# RoverMux.net
KiCad netlist of a schematic drawn in EAGLE
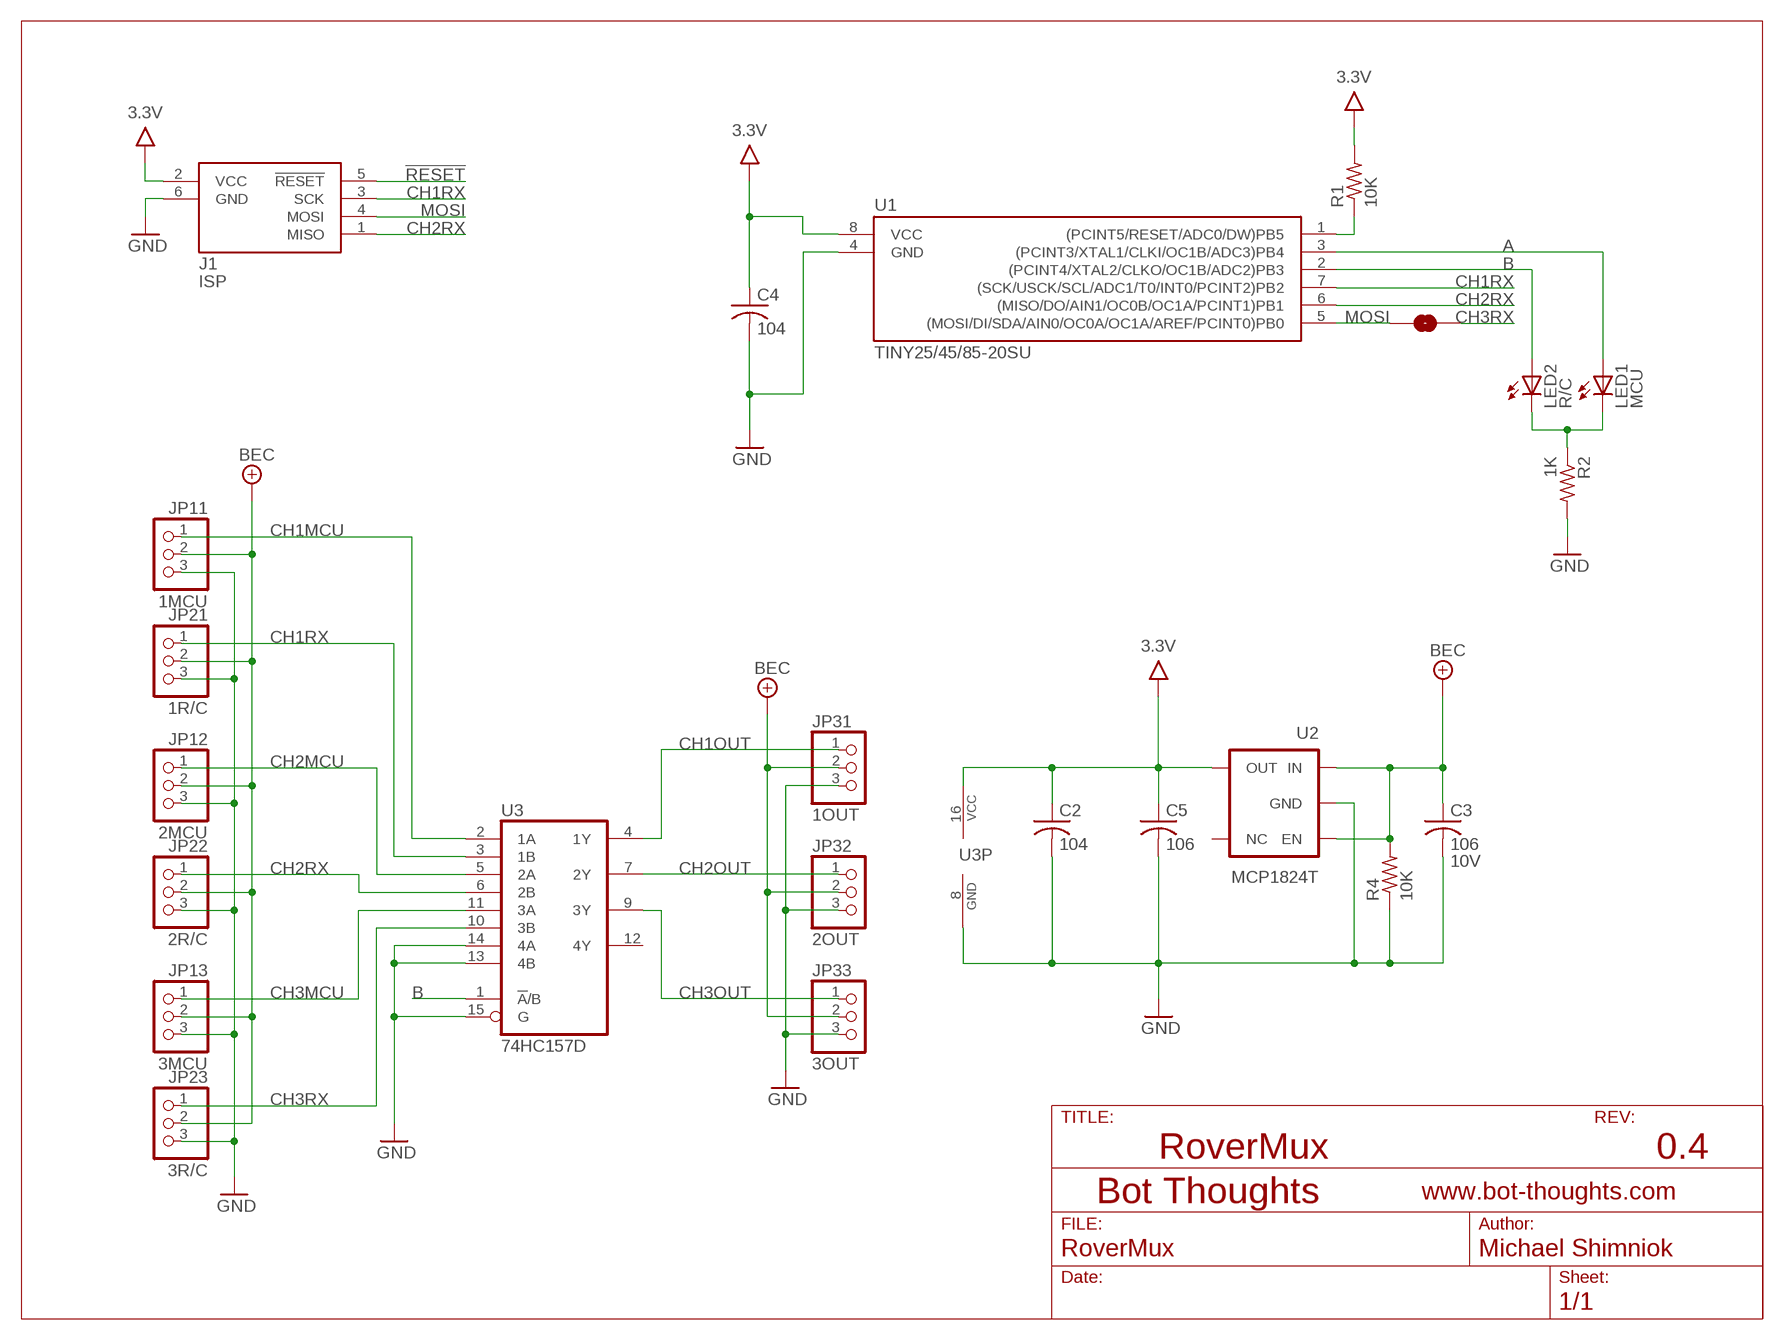
[diagram p0: schematic, sheet 1]

(export (version "E")
  (design (tool "Eeschema 10.0.6"))
  (components
    (comp (ref "C2")
      (value "104")
      (footprint "eagle-import:C0603")
      (fields (field (name "PARTNO") "C1608X7R1E104K080AA"))
      (libsource (lib "eagle-import") (part "C-USC0603"))
    )
    (comp (ref "C3")
      (value "106")
      (footprint "eagle-import:C0603")
      (fields (field (name "PARTNO") "CL10A106MP8NNNC") (field (name "VOLTAGE") "10V"))
      (libsource (lib "eagle-import") (part "C-USC0603"))
    )
    (comp (ref "C4")
      (value "104")
      (footprint "eagle-import:C0603")
      (fields (field (name "PARTNO") "C1608X7R1E104K080AA"))
      (libsource (lib "eagle-import") (part "C-USC0603"))
    )
    (comp (ref "C5")
      (value "106")
      (footprint "eagle-import:C0603")
      (fields (field (name "PARTNO") "CL10A106MP8NNNC"))
      (libsource (lib "eagle-import") (part "C-USC0603"))
    )
    (comp (ref "J1")
      (value "ISP")
      (footprint "eagle-import:CON6P2R")
      (libsource (lib "eagle-import") (part "AVRISP6"))
    )
    (comp (ref "JP11")
      (value "1MCU")
      (footprint "eagle-import:1X03-S")
      (libsource (lib "eagle-import") (part "PINHD-1X03_2.54-S"))
    )
    (comp (ref "JP12")
      (value "2MCU")
      (footprint "eagle-import:1X03-S")
      (libsource (lib "eagle-import") (part "PINHD-1X03_2.54-S"))
    )
    (comp (ref "JP13")
      (value "3MCU")
      (footprint "eagle-import:1X03-S")
      (libsource (lib "eagle-import") (part "PINHD-1X03_2.54-S"))
    )
    (comp (ref "JP21")
      (value "1R/C")
      (footprint "eagle-import:1X03-S")
      (libsource (lib "eagle-import") (part "PINHD-1X03_2.54-S"))
    )
    (comp (ref "JP22")
      (value "2R/C")
      (footprint "eagle-import:1X03-S")
      (libsource (lib "eagle-import") (part "PINHD-1X03_2.54-S"))
    )
    (comp (ref "JP23")
      (value "3R/C")
      (footprint "eagle-import:1X03-S")
      (libsource (lib "eagle-import") (part "PINHD-1X03_2.54-S"))
    )
    (comp (ref "JP31")
      (value "1OUT")
      (footprint "eagle-import:1X03-S")
      (libsource (lib "eagle-import") (part "PINHD-1X03_2.54-S"))
    )
    (comp (ref "JP32")
      (value "2OUT")
      (footprint "eagle-import:1X03-S")
      (libsource (lib "eagle-import") (part "PINHD-1X03_2.54-S"))
    )
    (comp (ref "JP33")
      (value "3OUT")
      (footprint "eagle-import:1X03-S")
      (libsource (lib "eagle-import") (part "PINHD-1X03_2.54-S"))
    )
    (comp (ref "LED1")
      (value "MCU")
      (footprint "eagle-import:CHIPLED_1206")
      (fields (field (name "PARTNO") "LH N974-KN-1"))
      (libsource (lib "eagle-import") (part "LEDCHIPLED_1206"))
    )
    (comp (ref "LED2")
      (value "R/C")
      (footprint "eagle-import:CHIPLED_1206")
      (fields (field (name "PARTNO") "LG N971-KN-1"))
      (libsource (lib "eagle-import") (part "LEDCHIPLED_1206"))
    )
    (comp (ref "R1")
      (value "10K")
      (footprint "eagle-import:R0603")
      (fields (field (name "PARTNO") "1622829-1"))
      (libsource (lib "eagle-import") (part "R-US_R0603"))
    )
    (comp (ref "R2")
      (value "1K")
      (footprint "eagle-import:R0603")
      (fields (field (name "PARTNO") "RC0603JR-07330RL"))
      (libsource (lib "eagle-import") (part "R-US_R0603"))
    )
    (comp (ref "R4")
      (value "10K")
      (footprint "eagle-import:R0603")
      (fields (field (name "PARTNO") "1622829-1"))
      (libsource (lib "eagle-import") (part "R-US_R0603"))
    )
    (comp (ref "SJ1")
      (value "CH3")
      (footprint "eagle-import:SJ_2S-NOTRACE")
      (libsource (lib "eagle-import") (part "SOLDERJUMPERNC2"))
    )
    (comp (ref "U1")
      (value "TINY25/45/85-20SU")
      (footprint "eagle-import:SOIC8")
      (libsource (lib "eagle-import") (part "TINY25/45/85-20SU"))
    )
    (comp (ref "U2")
      (value "MCP1824T")
      (footprint "eagle-import:SOT23-5")
      (fields (field (name "PARTNO") "MCP1824T-5002E/OT"))
      (libsource (lib "eagle-import") (part "MCP1801"))
    )
    (comp (ref "U3")
      (value "74HC157D")
      (footprint "eagle-import:SO16")
      (fields (field (name "PARTNO") "74HCT157D,652"))
      (libsource (lib "eagle-import") (part "74157DLS"))
    )
  )
  (nets
    (net (code "1") (name "/A") (class "Default")
      (node (ref "LED1") (pin "A") (pinfunction "A_A") (pintype "passive"))
      (node (ref "U1") (pin "3") (pinfunction "(PCINT3/XTAL1/CLKI/OC1B/ADC3)PB4_3") (pintype "bidirectional"))
    )
    (net (code "2") (name "/B") (class "Default")
      (node (ref "LED2") (pin "A") (pinfunction "A_A") (pintype "passive"))
      (node (ref "U1") (pin "2") (pinfunction "(PCINT4/XTAL2/CLKO/OC1B/ADC2)PB3_2") (pintype "bidirectional"))
      (node (ref "U3") (pin "1") (pinfunction "~{A}/B_1") (pintype "input"))
    )
    (net (code "3") (name "/CH1MCU") (class "Default")
      (node (ref "JP11") (pin "1") (pinfunction "1_1") (pintype "passive"))
      (node (ref "U3") (pin "2") (pinfunction "1A_2") (pintype "input"))
    )
    (net (code "4") (name "/CH1OUT") (class "Default")
      (node (ref "JP31") (pin "1") (pinfunction "1_1") (pintype "passive"))
      (node (ref "U3") (pin "4") (pinfunction "1Y_4") (pintype "output"))
    )
    (net (code "5") (name "/CH1RX") (class "Default")
      (node (ref "J1") (pin "3") (pinfunction "SCK_3") (pintype "output"))
      (node (ref "JP21") (pin "1") (pinfunction "1_1") (pintype "passive"))
      (node (ref "U1") (pin "7") (pinfunction "(SCK/USCK/SCL/ADC1/T0/INT0/PCINT2)PB2_7") (pintype "bidirectional"))
      (node (ref "U3") (pin "3") (pinfunction "1B_3") (pintype "input"))
    )
    (net (code "6") (name "/CH2MCU") (class "Default")
      (node (ref "JP12") (pin "1") (pinfunction "1_1") (pintype "passive"))
      (node (ref "U3") (pin "5") (pinfunction "2A_5") (pintype "input"))
    )
    (net (code "7") (name "/CH2OUT") (class "Default")
      (node (ref "JP32") (pin "1") (pinfunction "1_1") (pintype "passive"))
      (node (ref "U3") (pin "7") (pinfunction "2Y_7") (pintype "output"))
    )
    (net (code "8") (name "/CH2RX") (class "Default")
      (node (ref "J1") (pin "1") (pinfunction "MISO_1") (pintype "input"))
      (node (ref "JP22") (pin "1") (pinfunction "1_1") (pintype "passive"))
      (node (ref "U1") (pin "6") (pinfunction "(MISO/DO/AIN1/OC0B/OC1A/PCINT1)PB1_6") (pintype "bidirectional"))
      (node (ref "U3") (pin "6") (pinfunction "2B_6") (pintype "input"))
    )
    (net (code "9") (name "/CH3MCU") (class "Default")
      (node (ref "JP13") (pin "1") (pinfunction "1_1") (pintype "passive"))
      (node (ref "U3") (pin "11") (pinfunction "3A_11") (pintype "input"))
    )
    (net (code "10") (name "/CH3OUT") (class "Default")
      (node (ref "JP33") (pin "1") (pinfunction "1_1") (pintype "passive"))
      (node (ref "U3") (pin "9") (pinfunction "3Y_9") (pintype "output"))
    )
    (net (code "11") (name "/CH3RX") (class "Default")
      (node (ref "JP23") (pin "1") (pinfunction "1_1") (pintype "passive"))
      (node (ref "SJ1") (pin "2") (pinfunction "2_2") (pintype "passive"))
      (node (ref "U3") (pin "10") (pinfunction "3B_10") (pintype "input"))
    )
    (net (code "12") (name "/MOSI") (class "Default")
      (node (ref "J1") (pin "4") (pinfunction "MOSI_4") (pintype "output"))
      (node (ref "SJ1") (pin "1") (pinfunction "1_1") (pintype "passive"))
      (node (ref "U1") (pin "5") (pinfunction "(MOSI/DI/SDA/AIN0/OC0A/OC1A/AREF/PCINT0)PB0_5") (pintype "bidirectional"))
    )
    (net (code "13") (name "/~{RESET}") (class "Default")
      (node (ref "J1") (pin "5") (pinfunction "~{RESET}_5") (pintype "output"))
      (node (ref "R1") (pin "1") (pinfunction "1_1") (pintype "passive"))
      (node (ref "U1") (pin "1") (pinfunction "(PCINT5/RESET/ADC0/DW)PB5_1") (pintype "bidirectional"))
    )
    (net (code "14") (name "3.3V") (class "Default")
      (node (ref "C2") (pin "1") (pinfunction "1_1") (pintype "passive"))
      (node (ref "C4") (pin "1") (pinfunction "1_1") (pintype "passive"))
      (node (ref "C5") (pin "1") (pinfunction "1_1") (pintype "passive"))
      (node (ref "J1") (pin "2") (pinfunction "VCC_2") (pintype "power_in"))
      (node (ref "R1") (pin "2") (pinfunction "2_2") (pintype "passive"))
      (node (ref "U1") (pin "8") (pinfunction "VCC_8") (pintype "power_in"))
      (node (ref "U2") (pin "5") (pinfunction "OUT_5") (pintype "passive"))
      (node (ref "U3") (pin "16") (pinfunction "VCC_16") (pintype "power_in"))
    )
    (net (code "15") (name "BEC") (class "Default")
      (node (ref "C3") (pin "1") (pinfunction "1_1") (pintype "passive"))
      (node (ref "JP11") (pin "2") (pinfunction "2_2") (pintype "passive"))
      (node (ref "JP12") (pin "2") (pinfunction "2_2") (pintype "passive"))
      (node (ref "JP13") (pin "2") (pinfunction "2_2") (pintype "passive"))
      (node (ref "JP21") (pin "2") (pinfunction "2_2") (pintype "passive"))
      (node (ref "JP22") (pin "2") (pinfunction "2_2") (pintype "passive"))
      (node (ref "JP23") (pin "2") (pinfunction "2_2") (pintype "passive"))
      (node (ref "JP31") (pin "2") (pinfunction "2_2") (pintype "passive"))
      (node (ref "JP32") (pin "2") (pinfunction "2_2") (pintype "passive"))
      (node (ref "JP33") (pin "2") (pinfunction "2_2") (pintype "passive"))
      (node (ref "R4") (pin "2") (pinfunction "2_2") (pintype "passive"))
      (node (ref "U2") (pin "1") (pinfunction "IN_1") (pintype "input"))
      (node (ref "U2") (pin "3") (pinfunction "EN_3") (pintype "input"))
    )
    (net (code "16") (name "GND") (class "Default")
      (node (ref "C2") (pin "2") (pinfunction "2_2") (pintype "passive"))
      (node (ref "C3") (pin "2") (pinfunction "2_2") (pintype "passive"))
      (node (ref "C4") (pin "2") (pinfunction "2_2") (pintype "passive"))
      (node (ref "C5") (pin "2") (pinfunction "2_2") (pintype "passive"))
      (node (ref "J1") (pin "6") (pinfunction "GND_6") (pintype "power_in"))
      (node (ref "JP11") (pin "3") (pinfunction "3_3") (pintype "passive"))
      (node (ref "JP12") (pin "3") (pinfunction "3_3") (pintype "passive"))
      (node (ref "JP13") (pin "3") (pinfunction "3_3") (pintype "passive"))
      (node (ref "JP21") (pin "3") (pinfunction "3_3") (pintype "passive"))
      (node (ref "JP22") (pin "3") (pinfunction "3_3") (pintype "passive"))
      (node (ref "JP23") (pin "3") (pinfunction "3_3") (pintype "passive"))
      (node (ref "JP31") (pin "3") (pinfunction "3_3") (pintype "passive"))
      (node (ref "JP32") (pin "3") (pinfunction "3_3") (pintype "passive"))
      (node (ref "JP33") (pin "3") (pinfunction "3_3") (pintype "passive"))
      (node (ref "R2") (pin "2") (pinfunction "2_2") (pintype "passive"))
      (node (ref "R4") (pin "1") (pinfunction "1_1") (pintype "passive"))
      (node (ref "U1") (pin "4") (pinfunction "GND_4") (pintype "power_in"))
      (node (ref "U2") (pin "2") (pinfunction "GND_2") (pintype "input"))
      (node (ref "U3") (pin "13") (pinfunction "4B_13") (pintype "input"))
      (node (ref "U3") (pin "14") (pinfunction "4A_14") (pintype "input"))
      (node (ref "U3") (pin "15") (pinfunction "G_15") (pintype "input"))
      (node (ref "U3") (pin "8") (pinfunction "GND_8") (pintype "power_in"))
    )
    (net (code "17") (name "Net-(LED1-PadC)") (class "Default")
      (node (ref "LED1") (pin "C") (pinfunction "C_C") (pintype "passive"))
      (node (ref "LED2") (pin "C") (pinfunction "C_C") (pintype "passive"))
      (node (ref "R2") (pin "1") (pinfunction "1_1") (pintype "passive"))
    )
    (net (code "18") (name "unconnected-(U2-NC-Pad4)") (class "Default")
      (node (ref "U2") (pin "4") (pinfunction "NC_4") (pintype "input"))
    )
    (net (code "19") (name "unconnected-(U3A-4Y-Pad12)") (class "Default")
      (node (ref "U3") (pin "12") (pinfunction "4Y_12") (pintype "output"))
    )
  )
)
